# MI0283QT_v20.net
KiCad netlist of a schematic drawn in EAGLE
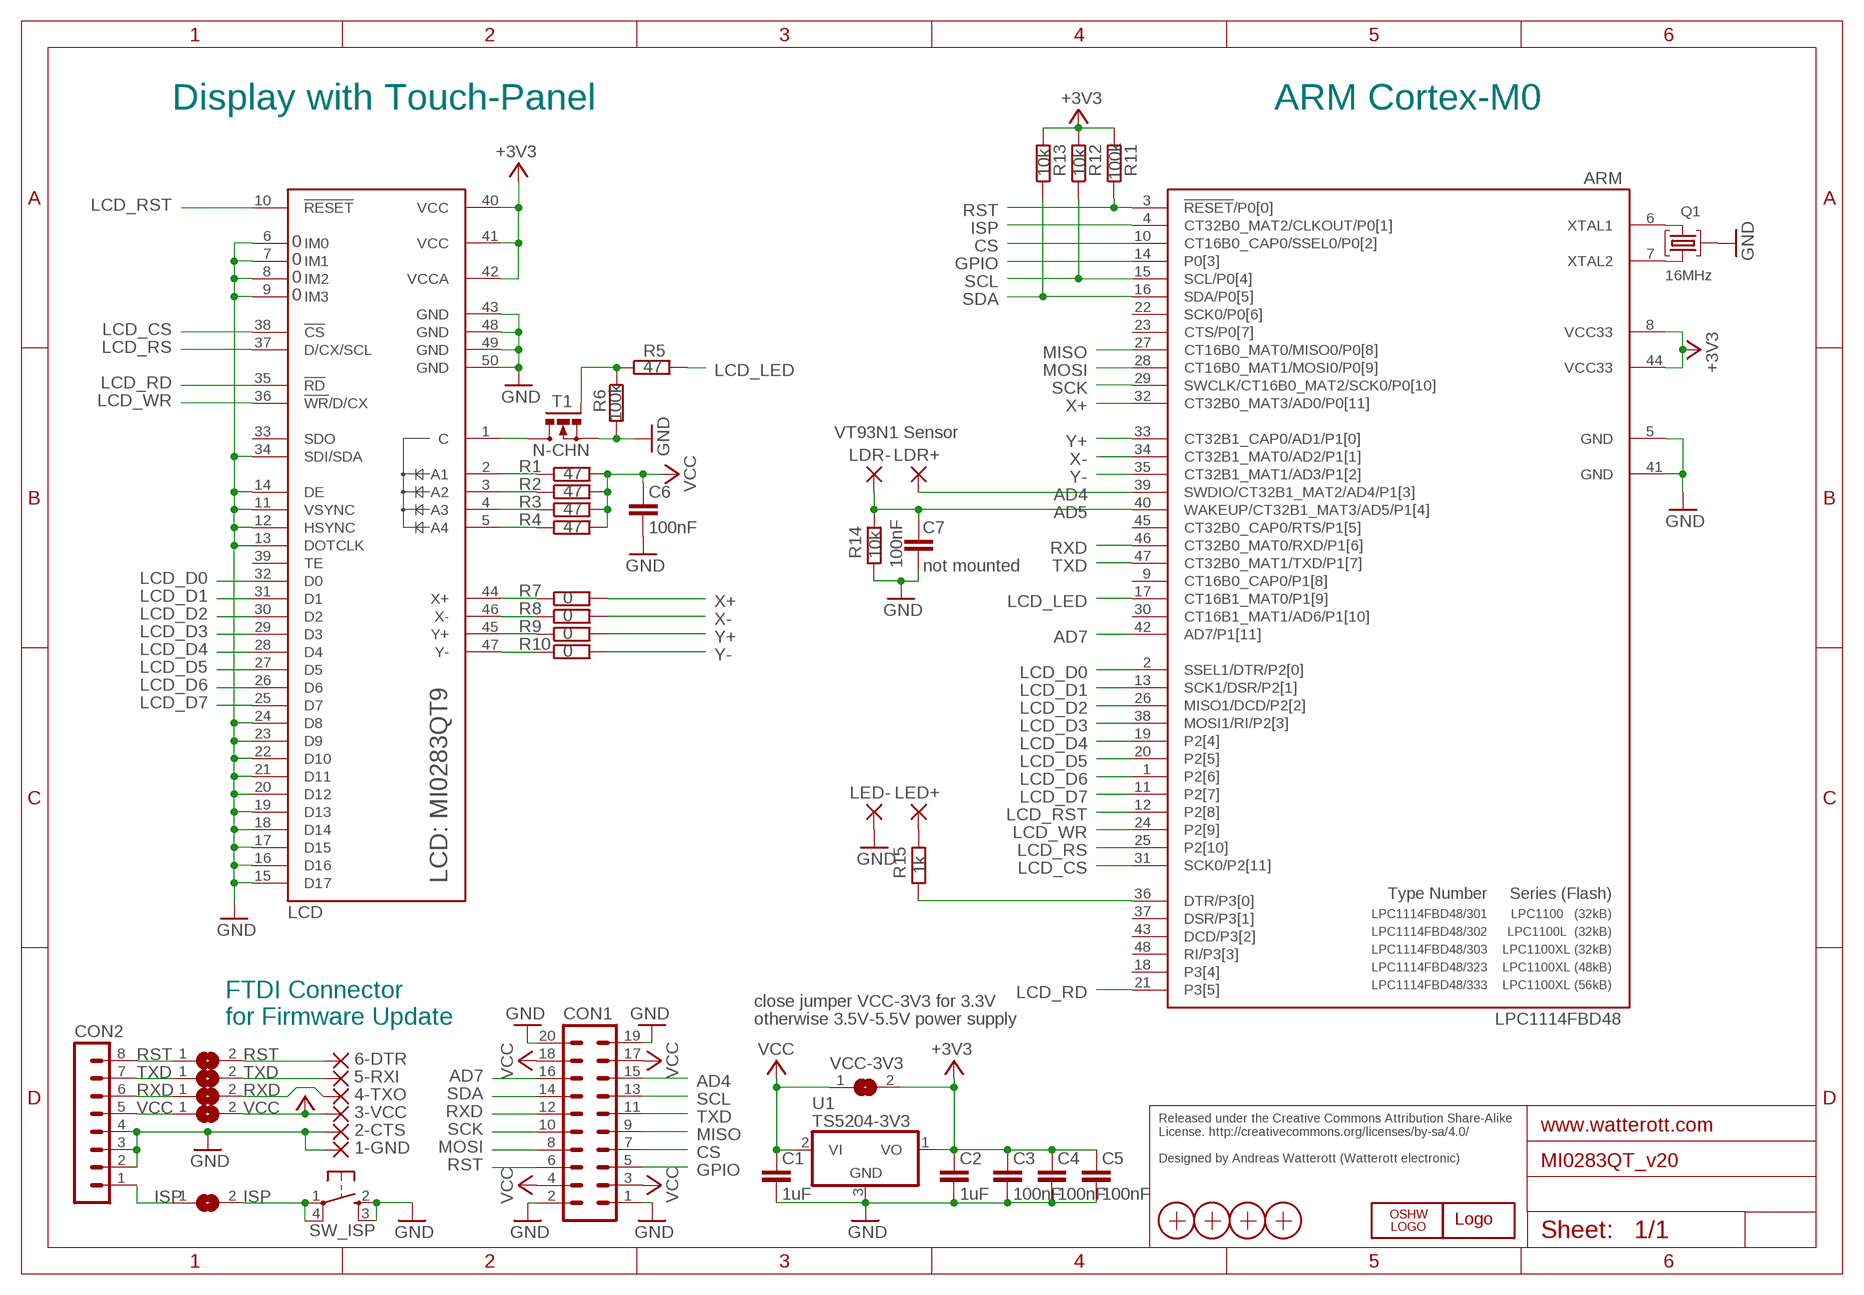
[diagram p0: schematic, sheet 1]

(export (version "E")
  (design (tool "Eeschema 10.0.6"))
  (components
    (comp (ref "1-GND")
      (value "WIREPADSMD1,27-254")
      (footprint "eagle-import:SMD1,27-2,54")
      (libsource (lib "eagle-import") (part "WIREPADSMD1,27-254"))
    )
    (comp (ref "2-CTS")
      (value "WIREPADSMD1,27-254")
      (footprint "eagle-import:SMD1,27-2,54")
      (libsource (lib "eagle-import") (part "WIREPADSMD1,27-254"))
    )
    (comp (ref "3-VCC")
      (value "WIREPADSMD1,27-254")
      (footprint "eagle-import:SMD1,27-2,54")
      (libsource (lib "eagle-import") (part "WIREPADSMD1,27-254"))
    )
    (comp (ref "4-TXO")
      (value "WIREPADSMD1,27-254")
      (footprint "eagle-import:SMD1,27-2,54")
      (libsource (lib "eagle-import") (part "WIREPADSMD1,27-254"))
    )
    (comp (ref "5-RXI")
      (value "WIREPADSMD1,27-254")
      (footprint "eagle-import:SMD1,27-2,54")
      (libsource (lib "eagle-import") (part "WIREPADSMD1,27-254"))
    )
    (comp (ref "6-DTR")
      (value "WIREPADSMD1,27-254")
      (footprint "eagle-import:SMD1,27-2,54")
      (libsource (lib "eagle-import") (part "WIREPADSMD1,27-254"))
    )
    (comp (ref "ARM")
      (value "LPC1114FBD48")
      (footprint "eagle-import:LQFP48")
      (libsource (lib "eagle-import") (part "LPC111X"))
    )
    (comp (ref "C1")
      (value "1uF")
      (footprint "eagle-import:C0603")
      (libsource (lib "eagle-import") (part "C-EUC0603"))
    )
    (comp (ref "C2")
      (value "1uF")
      (footprint "eagle-import:C0603")
      (libsource (lib "eagle-import") (part "C-EUC0603"))
    )
    (comp (ref "C3")
      (value "100nF")
      (footprint "eagle-import:C0603")
      (libsource (lib "eagle-import") (part "C-EUC0603"))
    )
    (comp (ref "C4")
      (value "100nF")
      (footprint "eagle-import:C0603")
      (libsource (lib "eagle-import") (part "C-EUC0603"))
    )
    (comp (ref "C5")
      (value "100nF")
      (footprint "eagle-import:C0603")
      (libsource (lib "eagle-import") (part "C-EUC0603"))
    )
    (comp (ref "C6")
      (value "100nF")
      (footprint "eagle-import:C0603")
      (libsource (lib "eagle-import") (part "C-EUC0603"))
    )
    (comp (ref "C7")
      (value "100nF")
      (footprint "eagle-import:C0603")
      (libsource (lib "eagle-import") (part "C-EUC0603"))
    )
    (comp (ref "CON1")
      (value "MA10-2")
      (footprint "eagle-import:MA10-2")
      (libsource (lib "eagle-import") (part "MA10-2"))
    )
    (comp (ref "CON2")
      (value "MA08-1")
      (footprint "eagle-import:MA08-1")
      (libsource (lib "eagle-import") (part "MA08-1"))
    )
    (comp (ref "ISP") (value "SJ") (footprint "eagle-import:SJ") (libsource (lib "eagle-import") (part "SJ")))
    (comp (ref "LCD")
      (value "MI0283QT9")
      (footprint "eagle-import:MI0283QT9")
      (libsource (lib "eagle-import") (part "MI0283QT9"))
    )
    (comp (ref "LDR+")
      (value "WIREPAD2,15/1,0")
      (footprint "eagle-import:2,15_1,0")
      (libsource (lib "eagle-import") (part "WIREPAD2,15/1,0"))
    )
    (comp (ref "LDR-")
      (value "WIREPAD2,15/1,0")
      (footprint "eagle-import:2,15_1,0")
      (libsource (lib "eagle-import") (part "WIREPAD2,15/1,0"))
    )
    (comp (ref "LED+")
      (value "WIREPAD2,15/1,0")
      (footprint "eagle-import:2,15_1,0")
      (libsource (lib "eagle-import") (part "WIREPAD2,15/1,0"))
    )
    (comp (ref "LED-")
      (value "WIREPAD2,15/1,0")
      (footprint "eagle-import:2,15_1,0")
      (libsource (lib "eagle-import") (part "WIREPAD2,15/1,0"))
    )
    (comp (ref "LOGO1")
      (value "OSHW_LOGO_6MILX0150-NT")
      (footprint "eagle-import:OSHW_6X150_NOTEXT")
      (libsource (lib "eagle-import") (part "OSHW_LOGO_6MILX0150-NT"))
    )
    (comp (ref "Q1")
      (value "16MHz")
      (footprint "eagle-import:SMD_OSC_35X15")
      (libsource (lib "eagle-import") (part "SMD_OSC2"))
    )
    (comp (ref "R1")
      (value "47")
      (footprint "eagle-import:R0603")
      (libsource (lib "eagle-import") (part "R-EU_R0603"))
    )
    (comp (ref "R2")
      (value "47")
      (footprint "eagle-import:R0603")
      (libsource (lib "eagle-import") (part "R-EU_R0603"))
    )
    (comp (ref "R3")
      (value "47")
      (footprint "eagle-import:R0603")
      (libsource (lib "eagle-import") (part "R-EU_R0603"))
    )
    (comp (ref "R4")
      (value "47")
      (footprint "eagle-import:R0603")
      (libsource (lib "eagle-import") (part "R-EU_R0603"))
    )
    (comp (ref "R5")
      (value "47")
      (footprint "eagle-import:R0603")
      (libsource (lib "eagle-import") (part "R-EU_R0603"))
    )
    (comp (ref "R6")
      (value "100k")
      (footprint "eagle-import:R0603")
      (libsource (lib "eagle-import") (part "R-EU_R0603"))
    )
    (comp (ref "R7")
      (value "0")
      (footprint "eagle-import:R0603")
      (libsource (lib "eagle-import") (part "R-EU_R0603"))
    )
    (comp (ref "R8")
      (value "0")
      (footprint "eagle-import:R0603")
      (libsource (lib "eagle-import") (part "R-EU_R0603"))
    )
    (comp (ref "R9")
      (value "0")
      (footprint "eagle-import:R0603")
      (libsource (lib "eagle-import") (part "R-EU_R0603"))
    )
    (comp (ref "R10")
      (value "0")
      (footprint "eagle-import:R0603")
      (libsource (lib "eagle-import") (part "R-EU_R0603"))
    )
    (comp (ref "R11")
      (value "100k")
      (footprint "eagle-import:R0603")
      (libsource (lib "eagle-import") (part "R-EU_R0603"))
    )
    (comp (ref "R12")
      (value "10k")
      (footprint "eagle-import:R0603")
      (libsource (lib "eagle-import") (part "R-EU_R0603"))
    )
    (comp (ref "R13")
      (value "10k")
      (footprint "eagle-import:R0603")
      (libsource (lib "eagle-import") (part "R-EU_R0603"))
    )
    (comp (ref "R14")
      (value "10k")
      (footprint "eagle-import:R0603")
      (libsource (lib "eagle-import") (part "R-EU_R0603"))
    )
    (comp (ref "R15")
      (value "1k")
      (footprint "eagle-import:R0603")
      (libsource (lib "eagle-import") (part "R-EU_R0603"))
    )
    (comp (ref "RST") (value "SJ") (footprint "eagle-import:SJ") (libsource (lib "eagle-import") (part "SJ")))
    (comp (ref "RXD") (value "SJ") (footprint "eagle-import:SJ") (libsource (lib "eagle-import") (part "SJ")))
    (comp (ref "SW_ISP")
      (value "SW_SMDS")
      (footprint "eagle-import:SW_SMD4@1")
      (libsource (lib "eagle-import") (part "SW_SMDS"))
    )
    (comp (ref "T1")
      (value "N-CHN")
      (footprint "eagle-import:MICRO3")
      (libsource (lib "eagle-import") (part "IRLML2502"))
    )
    (comp (ref "TXD") (value "SJ") (footprint "eagle-import:SJ") (libsource (lib "eagle-import") (part "SJ")))
    (comp (ref "U$1")
      (value "WE-LOGO")
      (footprint "eagle-import:WE-LOGO")
      (libsource (lib "eagle-import") (part "WE-LOGOPLACE"))
    )
    (comp (ref "U1")
      (value "TS5204-3V3")
      (footprint "eagle-import:SOT23")
      (libsource (lib "eagle-import") (part "TS5204"))
    )
    (comp (ref "VCC") (value "SJ") (footprint "eagle-import:SJ") (libsource (lib "eagle-import") (part "SJ")))
    (comp (ref "VCC-3V3")
      (value "SJ")
      (footprint "eagle-import:SJ")
      (libsource (lib "eagle-import") (part "SJ"))
    )
    (comp (ref "X1")
      (value "PASSER")
      (footprint "eagle-import:PASSER")
      (libsource (lib "eagle-import") (part "PASSER"))
    )
    (comp (ref "X2")
      (value "PASSER")
      (footprint "eagle-import:PASSER")
      (libsource (lib "eagle-import") (part "PASSER"))
    )
    (comp (ref "X3")
      (value "PASSER")
      (footprint "eagle-import:PASSER")
      (libsource (lib "eagle-import") (part "PASSER"))
    )
    (comp (ref "X4")
      (value "PASSER")
      (footprint "eagle-import:PASSER")
      (libsource (lib "eagle-import") (part "PASSER"))
    )
  )
  (nets
    (net (code "1") (name "+3V3") (class "Default")
      (node (ref "ARM") (pin "44") (pinfunction "VCC33_44") (pintype "bidirectional"))
      (node (ref "ARM") (pin "8") (pinfunction "VCC33_8") (pintype "bidirectional"))
      (node (ref "C2") (pin "1") (pinfunction "1_1") (pintype "passive"))
      (node (ref "C3") (pin "1") (pinfunction "1_1") (pintype "passive"))
      (node (ref "C4") (pin "1") (pinfunction "1_1") (pintype "passive"))
      (node (ref "C5") (pin "1") (pinfunction "1_1") (pintype "passive"))
      (node (ref "LCD") (pin "40") (pinfunction "VCC_40") (pintype "power_in"))
      (node (ref "LCD") (pin "41") (pinfunction "VCC_41") (pintype "power_in"))
      (node (ref "LCD") (pin "42") (pinfunction "VCCA_42") (pintype "power_in"))
      (node (ref "R11") (pin "2") (pinfunction "2_2") (pintype "passive"))
      (node (ref "R12") (pin "2") (pinfunction "2_2") (pintype "passive"))
      (node (ref "R13") (pin "2") (pinfunction "2_2") (pintype "passive"))
      (node (ref "U1") (pin "1") (pinfunction "VO_1") (pintype "passive"))
      (node (ref "VCC-3V3") (pin "2") (pinfunction "2_2") (pintype "passive"))
    )
    (net (code "2") (name "/AD4") (class "Default")
      (node (ref "ARM") (pin "39") (pinfunction "SWDIO/CT32B1_MAT2/AD4/P1[3]_39") (pintype "bidirectional"))
      (node (ref "CON1") (pin "15") (pinfunction "15_15") (pintype "passive"))
      (node (ref "LDR+") (pin "1") (pinfunction "P_1") (pintype "passive"))
    )
    (net (code "3") (name "/AD5") (class "Default")
      (node (ref "ARM") (pin "40") (pinfunction "WAKEUP/CT32B1_MAT3/AD5/P1[4]_40") (pintype "bidirectional"))
      (node (ref "C7") (pin "1") (pinfunction "1_1") (pintype "passive"))
      (node (ref "LDR-") (pin "1") (pinfunction "P_1") (pintype "passive"))
      (node (ref "R14") (pin "2") (pinfunction "2_2") (pintype "passive"))
    )
    (net (code "4") (name "/AD7") (class "Default")
      (node (ref "ARM") (pin "42") (pinfunction "AD7/P1[11]_42") (pintype "bidirectional"))
      (node (ref "CON1") (pin "16") (pinfunction "16_16") (pintype "passive"))
    )
    (net (code "5") (name "/CS") (class "Default")
      (node (ref "ARM") (pin "10") (pinfunction "CT16B0_CAP0/SSEL0/P0[2]_10") (pintype "bidirectional"))
      (node (ref "CON1") (pin "7") (pinfunction "7_7") (pintype "passive"))
    )
    (net (code "6") (name "/GPIO") (class "Default")
      (node (ref "ARM") (pin "14") (pinfunction "P0[3]_14") (pintype "bidirectional"))
      (node (ref "CON1") (pin "5") (pinfunction "5_5") (pintype "passive"))
    )
    (net (code "7") (name "/ISP") (class "Default")
      (node (ref "ARM") (pin "4") (pinfunction "CT32B0_MAT2/CLKOUT/P0[1]_4") (pintype "bidirectional"))
      (node (ref "ISP") (pin "2") (pinfunction "2_2") (pintype "passive"))
      (node (ref "SW_ISP") (pin "1") (pinfunction "P_1") (pintype "passive"))
      (node (ref "SW_ISP") (pin "4") (pinfunction "P1_4") (pintype "passive"))
    )
    (net (code "8") (name "/LCD_CS") (class "Default")
      (node (ref "ARM") (pin "31") (pinfunction "SCK0/P2[11]_31") (pintype "bidirectional"))
      (node (ref "LCD") (pin "38") (pinfunction "~{CS}_38") (pintype "input"))
    )
    (net (code "9") (name "/LCD_D0") (class "Default")
      (node (ref "ARM") (pin "2") (pinfunction "SSEL1/DTR/P2[0]_2") (pintype "bidirectional"))
      (node (ref "LCD") (pin "32") (pinfunction "D0_32") (pintype "input"))
    )
    (net (code "10") (name "/LCD_D1") (class "Default")
      (node (ref "ARM") (pin "13") (pinfunction "SCK1/DSR/P2[1]_13") (pintype "bidirectional"))
      (node (ref "LCD") (pin "31") (pinfunction "D1_31") (pintype "input"))
    )
    (net (code "11") (name "/LCD_D2") (class "Default")
      (node (ref "ARM") (pin "26") (pinfunction "MISO1/DCD/P2[2]_26") (pintype "bidirectional"))
      (node (ref "LCD") (pin "30") (pinfunction "D2_30") (pintype "input"))
    )
    (net (code "12") (name "/LCD_D3") (class "Default")
      (node (ref "ARM") (pin "38") (pinfunction "MOSI1/RI/P2[3]_38") (pintype "bidirectional"))
      (node (ref "LCD") (pin "29") (pinfunction "D3_29") (pintype "input"))
    )
    (net (code "13") (name "/LCD_D4") (class "Default")
      (node (ref "ARM") (pin "19") (pinfunction "P2[4]_19") (pintype "bidirectional"))
      (node (ref "LCD") (pin "28") (pinfunction "D4_28") (pintype "input"))
    )
    (net (code "14") (name "/LCD_D5") (class "Default")
      (node (ref "ARM") (pin "20") (pinfunction "P2[5]_20") (pintype "bidirectional"))
      (node (ref "LCD") (pin "27") (pinfunction "D5_27") (pintype "input"))
    )
    (net (code "15") (name "/LCD_D6") (class "Default")
      (node (ref "ARM") (pin "1") (pinfunction "P2[6]_1") (pintype "bidirectional"))
      (node (ref "LCD") (pin "26") (pinfunction "D6_26") (pintype "input"))
    )
    (net (code "16") (name "/LCD_D7") (class "Default")
      (node (ref "ARM") (pin "11") (pinfunction "P2[7]_11") (pintype "bidirectional"))
      (node (ref "LCD") (pin "25") (pinfunction "D7_25") (pintype "input"))
    )
    (net (code "17") (name "/LCD_LED") (class "Default")
      (node (ref "ARM") (pin "17") (pinfunction "CT16B1_MAT0/P1[9]_17") (pintype "bidirectional"))
      (node (ref "R5") (pin "2") (pinfunction "2_2") (pintype "passive"))
    )
    (net (code "18") (name "/LCD_RD") (class "Default")
      (node (ref "ARM") (pin "21") (pinfunction "P3[5]_21") (pintype "bidirectional"))
      (node (ref "LCD") (pin "35") (pinfunction "~{RD}_35") (pintype "input"))
    )
    (net (code "19") (name "/LCD_RS") (class "Default")
      (node (ref "ARM") (pin "25") (pinfunction "P2[10]_25") (pintype "bidirectional"))
      (node (ref "LCD") (pin "37") (pinfunction "D/CX/SCL_37") (pintype "input"))
    )
    (net (code "20") (name "/LCD_RST") (class "Default")
      (node (ref "ARM") (pin "12") (pinfunction "P2[8]_12") (pintype "bidirectional"))
      (node (ref "LCD") (pin "10") (pinfunction "~{RESET}_10") (pintype "input"))
    )
    (net (code "21") (name "/LCD_WR") (class "Default")
      (node (ref "ARM") (pin "24") (pinfunction "P2[9]_24") (pintype "bidirectional"))
      (node (ref "LCD") (pin "36") (pinfunction "~{WR}/D/CX_36") (pintype "input"))
    )
    (net (code "22") (name "/MISO") (class "Default")
      (node (ref "ARM") (pin "27") (pinfunction "CT16B0_MAT0/MISO0/P0[8]_27") (pintype "bidirectional"))
      (node (ref "CON1") (pin "9") (pinfunction "9_9") (pintype "passive"))
    )
    (net (code "23") (name "/MOSI") (class "Default")
      (node (ref "ARM") (pin "28") (pinfunction "CT16B0_MAT1/MOSI0/P0[9]_28") (pintype "bidirectional"))
      (node (ref "CON1") (pin "8") (pinfunction "8_8") (pintype "passive"))
    )
    (net (code "24") (name "/RST") (class "Default")
      (node (ref "6-DTR") (pin "1") (pinfunction "P_1") (pintype "passive"))
      (node (ref "ARM") (pin "3") (pinfunction "~{RESET}/P0[0]_3") (pintype "bidirectional"))
      (node (ref "CON1") (pin "6") (pinfunction "6_6") (pintype "passive"))
      (node (ref "R11") (pin "1") (pinfunction "1_1") (pintype "passive"))
      (node (ref "RST") (pin "2") (pinfunction "2_2") (pintype "passive"))
    )
    (net (code "25") (name "/RXD") (class "Default")
      (node (ref "4-TXO") (pin "1") (pinfunction "P_1") (pintype "passive"))
      (node (ref "ARM") (pin "46") (pinfunction "CT32B0_MAT0/RXD/P1[6]_46") (pintype "bidirectional"))
      (node (ref "CON1") (pin "12") (pinfunction "12_12") (pintype "passive"))
      (node (ref "RXD") (pin "2") (pinfunction "2_2") (pintype "passive"))
    )
    (net (code "26") (name "/SCK") (class "Default")
      (node (ref "ARM") (pin "29") (pinfunction "SWCLK/CT16B0_MAT2/SCK0/P0[10]_29") (pintype "bidirectional"))
      (node (ref "CON1") (pin "10") (pinfunction "10_10") (pintype "passive"))
    )
    (net (code "27") (name "/SCL") (class "Default")
      (node (ref "ARM") (pin "15") (pinfunction "SCL/P0[4]_15") (pintype "bidirectional"))
      (node (ref "CON1") (pin "13") (pinfunction "13_13") (pintype "passive"))
      (node (ref "R12") (pin "1") (pinfunction "1_1") (pintype "passive"))
    )
    (net (code "28") (name "/SDA") (class "Default")
      (node (ref "ARM") (pin "16") (pinfunction "SDA/P0[5]_16") (pintype "bidirectional"))
      (node (ref "CON1") (pin "14") (pinfunction "14_14") (pintype "passive"))
      (node (ref "R13") (pin "1") (pinfunction "1_1") (pintype "passive"))
    )
    (net (code "29") (name "/TXD") (class "Default")
      (node (ref "5-RXI") (pin "1") (pinfunction "P_1") (pintype "passive"))
      (node (ref "ARM") (pin "47") (pinfunction "CT32B0_MAT1/TXD/P1[7]_47") (pintype "bidirectional"))
      (node (ref "CON1") (pin "11") (pinfunction "11_11") (pintype "passive"))
      (node (ref "TXD") (pin "2") (pinfunction "2_2") (pintype "passive"))
    )
    (net (code "30") (name "/X+") (class "Default")
      (node (ref "ARM") (pin "32") (pinfunction "CT32B0_MAT3/AD0/P0[11]_32") (pintype "bidirectional"))
      (node (ref "R7") (pin "2") (pinfunction "2_2") (pintype "passive"))
    )
    (net (code "31") (name "/X-") (class "Default")
      (node (ref "ARM") (pin "34") (pinfunction "CT32B1_MAT0/AD2/P1[1]_34") (pintype "bidirectional"))
      (node (ref "R8") (pin "2") (pinfunction "2_2") (pintype "passive"))
    )
    (net (code "32") (name "/Y+") (class "Default")
      (node (ref "ARM") (pin "33") (pinfunction "CT32B1_CAP0/AD1/P1[0]_33") (pintype "bidirectional"))
      (node (ref "R9") (pin "2") (pinfunction "2_2") (pintype "passive"))
    )
    (net (code "33") (name "/Y-") (class "Default")
      (node (ref "ARM") (pin "35") (pinfunction "CT32B1_MAT1/AD3/P1[2]_35") (pintype "bidirectional"))
      (node (ref "R10") (pin "2") (pinfunction "2_2") (pintype "passive"))
    )
    (net (code "34") (name "GND") (class "Default")
      (node (ref "1-GND") (pin "1") (pinfunction "P_1") (pintype "passive"))
      (node (ref "2-CTS") (pin "1") (pinfunction "P_1") (pintype "passive"))
      (node (ref "ARM") (pin "41") (pinfunction "GND_41") (pintype "bidirectional"))
      (node (ref "ARM") (pin "5") (pinfunction "GND_5") (pintype "bidirectional"))
      (node (ref "C1") (pin "2") (pinfunction "2_2") (pintype "passive"))
      (node (ref "C2") (pin "2") (pinfunction "2_2") (pintype "passive"))
      (node (ref "C3") (pin "2") (pinfunction "2_2") (pintype "passive"))
      (node (ref "C4") (pin "2") (pinfunction "2_2") (pintype "passive"))
      (node (ref "C5") (pin "2") (pinfunction "2_2") (pintype "passive"))
      (node (ref "C6") (pin "2") (pinfunction "2_2") (pintype "passive"))
      (node (ref "C7") (pin "2") (pinfunction "2_2") (pintype "passive"))
      (node (ref "CON1") (pin "1") (pinfunction "1_1") (pintype "passive"))
      (node (ref "CON1") (pin "19") (pinfunction "19_19") (pintype "passive"))
      (node (ref "CON1") (pin "2") (pinfunction "2_2") (pintype "passive"))
      (node (ref "CON1") (pin "20") (pinfunction "20_20") (pintype "passive"))
      (node (ref "CON2") (pin "2") (pinfunction "2_2") (pintype "passive"))
      (node (ref "CON2") (pin "3") (pinfunction "3_3") (pintype "passive"))
      (node (ref "CON2") (pin "4") (pinfunction "4_4") (pintype "passive"))
      (node (ref "LCD") (pin "11") (pinfunction "VSYNC_11") (pintype "input"))
      (node (ref "LCD") (pin "12") (pinfunction "HSYNC_12") (pintype "input"))
      (node (ref "LCD") (pin "13") (pinfunction "DOTCLK_13") (pintype "input"))
      (node (ref "LCD") (pin "14") (pinfunction "DE_14") (pintype "input"))
      (node (ref "LCD") (pin "15") (pinfunction "D17_15") (pintype "input"))
      (node (ref "LCD") (pin "16") (pinfunction "D16_16") (pintype "input"))
      (node (ref "LCD") (pin "17") (pinfunction "D15_17") (pintype "input"))
      (node (ref "LCD") (pin "18") (pinfunction "D14_18") (pintype "input"))
      (node (ref "LCD") (pin "19") (pinfunction "D13_19") (pintype "input"))
      (node (ref "LCD") (pin "20") (pinfunction "D12_20") (pintype "input"))
      (node (ref "LCD") (pin "21") (pinfunction "D11_21") (pintype "input"))
      (node (ref "LCD") (pin "22") (pinfunction "D10_22") (pintype "input"))
      (node (ref "LCD") (pin "23") (pinfunction "D9_23") (pintype "input"))
      (node (ref "LCD") (pin "24") (pinfunction "D8_24") (pintype "input"))
      (node (ref "LCD") (pin "34") (pinfunction "SDI/SDA_34") (pintype "input"))
      (node (ref "LCD") (pin "43") (pinfunction "GND_43") (pintype "power_in"))
      (node (ref "LCD") (pin "48") (pinfunction "GND_48") (pintype "power_in"))
      (node (ref "LCD") (pin "49") (pinfunction "GND_49") (pintype "power_in"))
      (node (ref "LCD") (pin "50") (pinfunction "GND_50") (pintype "power_in"))
      (node (ref "LCD") (pin "6") (pinfunction "IM0_6") (pintype "input"))
      (node (ref "LCD") (pin "7") (pinfunction "IM1_7") (pintype "input"))
      (node (ref "LCD") (pin "8") (pinfunction "IM2_8") (pintype "input"))
      (node (ref "LCD") (pin "9") (pinfunction "IM3_9") (pintype "input"))
      (node (ref "LED-") (pin "1") (pinfunction "P_1") (pintype "passive"))
      (node (ref "Q1") (pin "GND") (pinfunction "GND_GND") (pintype "passive"))
      (node (ref "R14") (pin "1") (pinfunction "1_1") (pintype "passive"))
      (node (ref "R6") (pin "2") (pinfunction "2_2") (pintype "passive"))
      (node (ref "SW_ISP") (pin "2") (pinfunction "S_2") (pintype "passive"))
      (node (ref "SW_ISP") (pin "3") (pinfunction "S1_3") (pintype "passive"))
      (node (ref "T1") (pin "2") (pinfunction "S_2") (pintype "passive"))
      (node (ref "U1") (pin "3") (pinfunction "GND_3") (pintype "passive"))
    )
    (net (code "35") (name "Net-(ARM-DTR{slash}P3[0])") (class "Default")
      (node (ref "ARM") (pin "36") (pinfunction "DTR/P3[0]_36") (pintype "bidirectional"))
      (node (ref "R15") (pin "1") (pinfunction "1_1") (pintype "passive"))
    )
    (net (code "36") (name "Net-(ARM-XTAL1)") (class "Default")
      (node (ref "ARM") (pin "6") (pinfunction "XTAL1_6") (pintype "bidirectional"))
      (node (ref "Q1") (pin "2") (pinfunction "2_2") (pintype "passive"))
    )
    (net (code "37") (name "Net-(ARM-XTAL2)") (class "Default")
      (node (ref "ARM") (pin "7") (pinfunction "XTAL2_7") (pintype "bidirectional"))
      (node (ref "Q1") (pin "1") (pinfunction "1_1") (pintype "passive"))
    )
    (net (code "38") (name "Net-(CON2-Pad1)") (class "Default")
      (node (ref "CON2") (pin "1") (pinfunction "1_1") (pintype "passive"))
      (node (ref "ISP") (pin "1") (pinfunction "1_1") (pintype "passive"))
    )
    (net (code "39") (name "Net-(CON2-Pad5)") (class "Default")
      (node (ref "CON2") (pin "5") (pinfunction "5_5") (pintype "passive"))
      (node (ref "VCC") (pin "1") (pinfunction "1_1") (pintype "passive"))
    )
    (net (code "40") (name "Net-(CON2-Pad6)") (class "Default")
      (node (ref "CON2") (pin "6") (pinfunction "6_6") (pintype "passive"))
      (node (ref "RXD") (pin "1") (pinfunction "1_1") (pintype "passive"))
    )
    (net (code "41") (name "Net-(CON2-Pad7)") (class "Default")
      (node (ref "CON2") (pin "7") (pinfunction "7_7") (pintype "passive"))
      (node (ref "TXD") (pin "1") (pinfunction "1_1") (pintype "passive"))
    )
    (net (code "42") (name "Net-(CON2-Pad8)") (class "Default")
      (node (ref "CON2") (pin "8") (pinfunction "8_8") (pintype "passive"))
      (node (ref "RST") (pin "1") (pinfunction "1_1") (pintype "passive"))
    )
    (net (code "43") (name "Net-(LCD-A1)") (class "Default")
      (node (ref "LCD") (pin "2") (pinfunction "A1_2") (pintype "power_in"))
      (node (ref "R1") (pin "1") (pinfunction "1_1") (pintype "passive"))
    )
    (net (code "44") (name "Net-(LCD-A2)") (class "Default")
      (node (ref "LCD") (pin "3") (pinfunction "A2_3") (pintype "power_in"))
      (node (ref "R2") (pin "1") (pinfunction "1_1") (pintype "passive"))
    )
    (net (code "45") (name "Net-(LCD-A3)") (class "Default")
      (node (ref "LCD") (pin "4") (pinfunction "A3_4") (pintype "power_in"))
      (node (ref "R3") (pin "1") (pinfunction "1_1") (pintype "passive"))
    )
    (net (code "46") (name "Net-(LCD-A4)") (class "Default")
      (node (ref "LCD") (pin "5") (pinfunction "A4_5") (pintype "power_in"))
      (node (ref "R4") (pin "1") (pinfunction "1_1") (pintype "passive"))
    )
    (net (code "47") (name "Net-(LCD-C)") (class "Default")
      (node (ref "LCD") (pin "1") (pinfunction "C_1") (pintype "power_in"))
      (node (ref "T1") (pin "3") (pinfunction "D_3") (pintype "passive"))
    )
    (net (code "48") (name "Net-(LCD-X+)") (class "Default")
      (node (ref "LCD") (pin "44") (pinfunction "X+_44") (pintype "passive"))
      (node (ref "R7") (pin "1") (pinfunction "1_1") (pintype "passive"))
    )
    (net (code "49") (name "Net-(LCD-X-)") (class "Default")
      (node (ref "LCD") (pin "46") (pinfunction "X-_46") (pintype "passive"))
      (node (ref "R8") (pin "1") (pinfunction "1_1") (pintype "passive"))
    )
    (net (code "50") (name "Net-(LCD-Y+)") (class "Default")
      (node (ref "LCD") (pin "45") (pinfunction "Y+_45") (pintype "passive"))
      (node (ref "R9") (pin "1") (pinfunction "1_1") (pintype "passive"))
    )
    (net (code "51") (name "Net-(LCD-Y-)") (class "Default")
      (node (ref "LCD") (pin "47") (pinfunction "Y-_47") (pintype "passive"))
      (node (ref "R10") (pin "1") (pinfunction "1_1") (pintype "passive"))
    )
    (net (code "52") (name "Net-(LED+-P)") (class "Default")
      (node (ref "LED+") (pin "1") (pinfunction "P_1") (pintype "passive"))
      (node (ref "R15") (pin "2") (pinfunction "2_2") (pintype "passive"))
    )
    (net (code "53") (name "Net-(T1-G)") (class "Default")
      (node (ref "R5") (pin "1") (pinfunction "1_1") (pintype "passive"))
      (node (ref "R6") (pin "1") (pinfunction "1_1") (pintype "passive"))
      (node (ref "T1") (pin "1") (pinfunction "G_1") (pintype "passive"))
    )
    (net (code "54") (name "VCC") (class "Default")
      (node (ref "3-VCC") (pin "1") (pinfunction "P_1") (pintype "passive"))
      (node (ref "C1") (pin "1") (pinfunction "1_1") (pintype "passive"))
      (node (ref "C6") (pin "1") (pinfunction "1_1") (pintype "passive"))
      (node (ref "CON1") (pin "17") (pinfunction "17_17") (pintype "passive"))
      (node (ref "CON1") (pin "18") (pinfunction "18_18") (pintype "passive"))
      (node (ref "CON1") (pin "3") (pinfunction "3_3") (pintype "passive"))
      (node (ref "CON1") (pin "4") (pinfunction "4_4") (pintype "passive"))
      (node (ref "R1") (pin "2") (pinfunction "2_2") (pintype "passive"))
      (node (ref "R2") (pin "2") (pinfunction "2_2") (pintype "passive"))
      (node (ref "R3") (pin "2") (pinfunction "2_2") (pintype "passive"))
      (node (ref "R4") (pin "2") (pinfunction "2_2") (pintype "passive"))
      (node (ref "U1") (pin "2") (pinfunction "VI_2") (pintype "input"))
      (node (ref "VCC") (pin "2") (pinfunction "2_2") (pintype "passive"))
      (node (ref "VCC-3V3") (pin "1") (pinfunction "1_1") (pintype "passive"))
    )
    (net (code "55") (name "unconnected-(ARM-CT16B0_CAP0{slash}P1[8]-Pad9)") (class "Default")
      (node (ref "ARM") (pin "9") (pinfunction "CT16B0_CAP0/P1[8]_9") (pintype "bidirectional"))
    )
    (net (code "56") (name "unconnected-(ARM-CT16B1_MAT1{slash}AD6{slash}P1[10]-Pad30)") (class "Default")
      (node (ref "ARM") (pin "30") (pinfunction "CT16B1_MAT1/AD6/P1[10]_30") (pintype "bidirectional"))
    )
    (net (code "57") (name "unconnected-(ARM-CT32B0_CAP0{slash}RTS{slash}P1[5]-Pad45)") (class "Default")
      (node (ref "ARM") (pin "45") (pinfunction "CT32B0_CAP0/RTS/P1[5]_45") (pintype "bidirectional"))
    )
    (net (code "58") (name "unconnected-(ARM-CTS{slash}P0[7]-Pad23)") (class "Default")
      (node (ref "ARM") (pin "23") (pinfunction "CTS/P0[7]_23") (pintype "bidirectional"))
    )
    (net (code "59") (name "unconnected-(ARM-DCD{slash}P3[2]-Pad43)") (class "Default")
      (node (ref "ARM") (pin "43") (pinfunction "DCD/P3[2]_43") (pintype "bidirectional"))
    )
    (net (code "60") (name "unconnected-(ARM-DSR{slash}P3[1]-Pad37)") (class "Default")
      (node (ref "ARM") (pin "37") (pinfunction "DSR/P3[1]_37") (pintype "bidirectional"))
    )
    (net (code "61") (name "unconnected-(ARM-P3[4]-Pad18)") (class "Default")
      (node (ref "ARM") (pin "18") (pinfunction "P3[4]_18") (pintype "bidirectional"))
    )
    (net (code "62") (name "unconnected-(ARM-RI{slash}P3[3]-Pad48)") (class "Default")
      (node (ref "ARM") (pin "48") (pinfunction "RI/P3[3]_48") (pintype "bidirectional"))
    )
    (net (code "63") (name "unconnected-(ARM-SCK0{slash}P0[6]-Pad22)") (class "Default")
      (node (ref "ARM") (pin "22") (pinfunction "SCK0/P0[6]_22") (pintype "bidirectional"))
    )
    (net (code "64") (name "unconnected-(LCD-SDO-Pad33)") (class "Default")
      (node (ref "LCD") (pin "33") (pinfunction "SDO_33") (pintype "output"))
    )
    (net (code "65") (name "unconnected-(LCD-TE-Pad39)") (class "Default")
      (node (ref "LCD") (pin "39") (pinfunction "TE_39") (pintype "output"))
    )
  )
)
